# Circuit_Schematic.net
KiCad netlist of a schematic drawn in Altium Designer
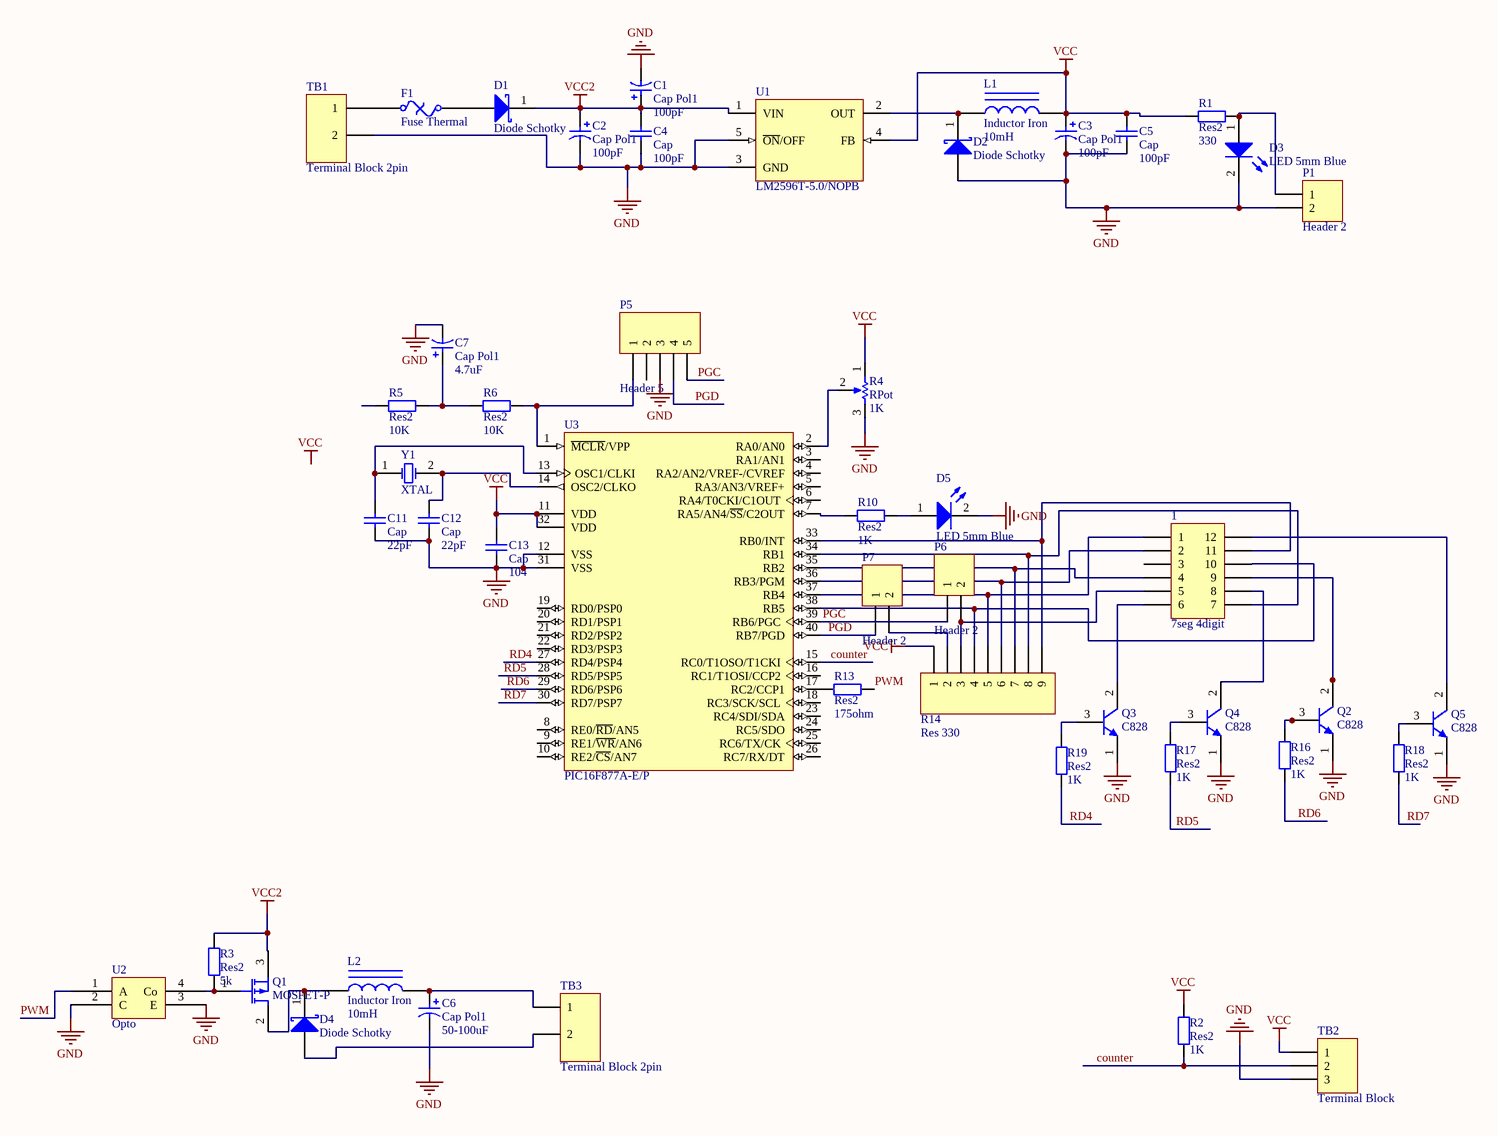
[diagram p0: Circuit Schematic.SchDoc]

(export (version "E")
  (design (tool "Eeschema 10.0.6"))
  (components
    (comp (ref "1")
      (value "7seg 4digit")
      (footprint "LEDDIP-12/QUAD")
      (description "Header, 6-Pin, Dual row")
      (fields (field (name "PUBLISHER") "Altium Limited"))
      (libsource (lib "Manh") (part "7seg 4digit"))
    )
    (comp (ref "C1")
      (value "Cap Pol1")
      (footprint "Manh:CAPPR2-5x7")
      (description "Polarized Capacitor (Radial)")
      (fields (field (name "ALTIUM_VALUE") "100pF") (field (name "PUBLISHER") "Altium Limited"))
      (libsource (lib "Manh") (part "Cap Pol1"))
    )
    (comp (ref "C2")
      (value "Cap Pol1")
      (footprint "CAPPR2.5-6.3x5/H.9")
      (description "Polarized Capacitor (Radial)")
      (fields (field (name "ALTIUM_VALUE") "100pF") (field (name "PUBLISHER") "Altium Limited"))
      (libsource (lib "Manh") (part "Cap Pol1"))
    )
    (comp (ref "C3")
      (value "Cap Pol1")
      (footprint "CAPPR2.5-6.3x5/H.9")
      (description "Polarized Capacitor (Radial)")
      (fields (field (name "ALTIUM_VALUE") "100pF") (field (name "PUBLISHER") "Altium Limited"))
      (libsource (lib "Manh") (part "Cap Pol1"))
    )
    (comp (ref "C4")
      (value "Cap")
      (footprint "CAPNTO3.18-4.83x2.67")
      (description "Capacitor")
      (fields (field (name "ALTIUM_VALUE") "100pF") (field (name "PUBLISHER") "Altium Limited"))
      (libsource (lib "Manh") (part "Cap"))
    )
    (comp (ref "C5")
      (value "Cap")
      (footprint "CAPNTO3.18-4.83x2.67")
      (description "Capacitor")
      (fields (field (name "ALTIUM_VALUE") "100pF") (field (name "PUBLISHER") "Altium Limited"))
      (libsource (lib "Manh") (part "Cap"))
    )
    (comp (ref "C6")
      (value "Cap Pol1")
      (footprint "CAPPR2.5-6.3x5/H.9")
      (description "Polarized Capacitor (Radial)")
      (fields (field (name "ALTIUM_VALUE") "50-100uF") (field (name "PUBLISHER") "Altium Limited"))
      (libsource (lib "Manh") (part "Cap Pol1"))
    )
    (comp (ref "C7")
      (value "Cap Pol1")
      (footprint "CAPPR2-5x7")
      (description "Polarized Capacitor (Radial)")
      (fields (field (name "ALTIUM_VALUE") "4.7uF") (field (name "PUBLISHER") "Altium Limited"))
      (libsource (lib "Manh") (part "Cap Pol1"))
    )
    (comp (ref "C11")
      (value "Cap")
      (footprint "CAPNTO3.18-4.83x2.67")
      (description "Capacitor")
      (fields (field (name "ALTIUM_VALUE") "22pF") (field (name "PUBLISHER") "Altium Limited"))
      (libsource (lib "Manh") (part "Cap"))
    )
    (comp (ref "C12")
      (value "Cap")
      (footprint "CAPNTO3.18-4.83x2.67")
      (description "Capacitor")
      (fields (field (name "ALTIUM_VALUE") "22pF") (field (name "PUBLISHER") "Altium Limited"))
      (libsource (lib "Manh") (part "Cap"))
    )
    (comp (ref "C13")
      (value "Cap")
      (footprint "CAPNTO3.18-4.83x2.67")
      (description "Capacitor")
      (fields (field (name "ALTIUM_VALUE") "104") (field (name "PUBLISHER") "Altium Limited"))
      (libsource (lib "Manh") (part "Cap"))
    )
    (comp (ref "D1")
      (value "Diode Schotky")
      (footprint "DO-201AD")
      (description "Schottky Rectifier")
      (fields (field (name "PUBLISHER") "Altium Limited"))
      (libsource (lib "Manh") (part "Diode Schotky"))
    )
    (comp (ref "D2")
      (value "Diode Schotky")
      (footprint "DO-41")
      (description "Schottky Rectifier")
      (fields (field (name "PUBLISHER") "Altium Limited"))
      (libsource (lib "Manh") (part "Diode Schotky"))
    )
    (comp (ref "D3")
      (value "LED 5mm Blue")
      (footprint "LED 5mm Blue")
      (description "Typical INFRARED GaAs LED")
      (fields (field (name "PUBLISHER") "Altium Limited"))
      (libsource (lib "Manh") (part "LED 5mm Blue"))
    )
    (comp (ref "D4")
      (value "Diode Schotky")
      (footprint "DO-41")
      (description "Schottky Rectifier")
      (fields (field (name "PUBLISHER") "Altium Limited"))
      (libsource (lib "Manh") (part "Diode Schotky"))
    )
    (comp (ref "D5")
      (value "LED 5mm Blue")
      (footprint "LED 5mm Blue")
      (description "Typical INFRARED GaAs LED")
      (fields (field (name "PUBLISHER") "Altium Limited"))
      (libsource (lib "Manh") (part "LED 5mm Blue"))
    )
    (comp (ref "F1")
      (value "Fuse Thermal")
      (footprint "PIN-W2/E2.8 -Manh")
      (description "Thermal Fuse")
      (fields (field (name "PUBLISHER") "Altium Limited"))
      (libsource (lib "Manh") (part "Fuse Thermal"))
    )
    (comp (ref "L1")
      (value "Inductor Iron")
      (footprint "Inductor power")
      (description "Magnetic-Core Inductor")
      (fields (field (name "ALTIUM_VALUE") "10mH") (field (name "PUBLISHER") "Altium Limited"))
      (libsource (lib "Manh") (part "Inductor Iron"))
    )
    (comp (ref "L2")
      (value "Inductor Iron")
      (footprint "Inductor power")
      (description "Magnetic-Core Inductor")
      (fields (field (name "ALTIUM_VALUE") "10mH") (field (name "PUBLISHER") "Altium Limited"))
      (libsource (lib "Manh") (part "Inductor Iron"))
    )
    (comp (ref "P1")
      (value "Header 2")
      (footprint "HDR1X2")
      (description "Header, 2-Pin")
      (fields (field (name "PUBLISHER") "Altium Limited"))
      (libsource (lib "Manh") (part "Header 2"))
    )
    (comp (ref "P5")
      (value "Header 5")
      (footprint "HDR1X5")
      (description "Header, 5-Pin")
      (fields (field (name "PUBLISHER") "Altium Limited"))
      (libsource (lib "Manh") (part "Header 5"))
    )
    (comp (ref "P6")
      (value "Header 2")
      (footprint "HDR1X2")
      (description "Header, 2-Pin")
      (fields (field (name "PUBLISHER") "Altium Limited"))
      (libsource (lib "") (part "Header 2_1"))
    )
    (comp (ref "P7")
      (value "Header 2")
      (footprint "HDR1X2")
      (description "Header, 2-Pin")
      (fields (field (name "PUBLISHER") "Altium Limited"))
      (libsource (lib "") (part "Header 2_1"))
    )
    (comp (ref "Q1")
      (value "MOSFET-P")
      (footprint "TO 220")
      (description "P-Channel MOSFET")
      (fields (field (name "PUBLISHER") "Altium Limited"))
      (libsource (lib "Manh") (part "MOSFET-P"))
    )
    (comp (ref "Q2")
      (value "C828")
      (footprint "TO-92-manh")
      (description "NPN General Purpose Amplifier")
      (fields (field (name "PUBLISHER") "Altium Limited"))
      (libsource (lib "Manh") (part "C828"))
    )
    (comp (ref "Q3")
      (value "C828")
      (footprint "TO-92-manh")
      (description "NPN General Purpose Amplifier")
      (fields (field (name "PUBLISHER") "Altium Limited"))
      (libsource (lib "Manh") (part "C828"))
    )
    (comp (ref "Q4")
      (value "C828")
      (footprint "TO-92-manh")
      (description "NPN General Purpose Amplifier")
      (fields (field (name "PUBLISHER") "Altium Limited"))
      (libsource (lib "Manh") (part "C828"))
    )
    (comp (ref "Q5")
      (value "C828")
      (footprint "TO-92-manh")
      (description "NPN General Purpose Amplifier")
      (fields (field (name "PUBLISHER") "Altium Limited"))
      (libsource (lib "Manh") (part "C828"))
    )
    (comp (ref "R1")
      (value "Res2")
      (footprint "AXIAL-0.4")
      (description "Resistor")
      (fields (field (name "ALTIUM_VALUE") "330") (field (name "PUBLISHER") "Altium Limited"))
      (libsource (lib "Manh") (part "Res2"))
    )
    (comp (ref "R2")
      (value "Res2")
      (footprint "AXIAL-0.4")
      (description "Resistor")
      (fields (field (name "ALTIUM_VALUE") "1K") (field (name "PUBLISHER") "Altium Limited"))
      (libsource (lib "") (part "Res2_2"))
    )
    (comp (ref "R3")
      (value "Res2")
      (footprint "AXIAL-0.4")
      (description "Resistor")
      (fields (field (name "ALTIUM_VALUE") "5k") (field (name "PUBLISHER") "Altium Limited"))
      (libsource (lib "") (part "Res2_1"))
    )
    (comp (ref "R4")
      (value "RPot")
      (footprint "Variable Resistor")
      (description "Potentiometer")
      (fields (field (name "ALTIUM_VALUE") "1K") (field (name "PUBLISHER") "Altium Limited"))
      (libsource (lib "Manh") (part "RPot"))
    )
    (comp (ref "R5")
      (value "Res2")
      (footprint "AXIAL-0.4")
      (description "Resistor")
      (fields (field (name "ALTIUM_VALUE") "10K") (field (name "PUBLISHER") "Altium Limited"))
      (libsource (lib "Manh") (part "Res2"))
    )
    (comp (ref "R6")
      (value "Res2")
      (footprint "AXIAL-0.4")
      (description "Resistor")
      (fields (field (name "ALTIUM_VALUE") "10K") (field (name "PUBLISHER") "Altium Limited"))
      (libsource (lib "Manh") (part "Res2"))
    )
    (comp (ref "R10")
      (value "Res2")
      (footprint "AXIAL-0.4")
      (description "Resistor")
      (fields (field (name "ALTIUM_VALUE") "1K") (field (name "PUBLISHER") "Altium Limited"))
      (libsource (lib "Manh") (part "Res2"))
    )
    (comp (ref "R13")
      (value "Res2")
      (footprint "AXIAL-0.4")
      (description "Resistor")
      (fields (field (name "ALTIUM_VALUE") "175ohm") (field (name "PUBLISHER") "Altium Limited"))
      (libsource (lib "") (part "Res2_3"))
    )
    (comp (ref "R14")
      (value "Res 330")
      (footprint "Res array 8")
      (description "Header, 9-Pin")
      (fields (field (name "PUBLISHER") "Altium Limited"))
      (libsource (lib "Manh") (part "Res array 8"))
    )
    (comp (ref "R16")
      (value "Res2")
      (footprint "AXIAL-0.4")
      (description "Resistor")
      (fields (field (name "ALTIUM_VALUE") "1K") (field (name "PUBLISHER") "Altium Limited"))
      (libsource (lib "") (part "Res2_1"))
    )
    (comp (ref "R17")
      (value "Res2")
      (footprint "AXIAL-0.4")
      (description "Resistor")
      (fields (field (name "ALTIUM_VALUE") "1K") (field (name "PUBLISHER") "Altium Limited"))
      (libsource (lib "") (part "Res2_1"))
    )
    (comp (ref "R18")
      (value "Res2")
      (footprint "AXIAL-0.4")
      (description "Resistor")
      (fields (field (name "ALTIUM_VALUE") "1K") (field (name "PUBLISHER") "Altium Limited"))
      (libsource (lib "") (part "Res2_1"))
    )
    (comp (ref "R19")
      (value "Res2")
      (footprint "AXIAL-0.4")
      (description "Resistor")
      (fields (field (name "ALTIUM_VALUE") "1K") (field (name "PUBLISHER") "Altium Limited"))
      (libsource (lib "") (part "Res2_1"))
    )
    (comp (ref "TB1")
      (value "Terminal Block 2pin")
      (footprint "Screw Terminal Block 2pin 5mm")
      (fields (field (name "PUBLISHER") "Altium Limited"))
      (libsource (lib "Manh") (part "Terminal Block 2pin"))
    )
    (comp (ref "TB2")
      (value "Terminal Block")
      (footprint "Screw Terminal Block 3pin 5mm")
      (description "Terminal Block 3pin")
      (fields (field (name "PUBLISHER") "Altium Limited"))
      (libsource (lib "Manh") (part "Terminal Block 3pin"))
    )
    (comp (ref "TB3")
      (value "Terminal Block 2pin")
      (footprint "Screw Terminal Block 2pin 5mm")
      (fields (field (name "PUBLISHER") "Altium Limited"))
      (libsource (lib "") (part "Terminal Block 2pin_1"))
    )
    (comp (ref "U1")
      (value "LM2596T-5.0/NOPB")
      (footprint "T05D")
      (description "SIMPLE SWITCHER® Power Converter 150 KHz 3A Step-Down Voltage Regulator, 5-pin TO-220, Pb-Free")
      (fields
        (field (name "MANUFACTURER") "National Semiconductor")
        (field (name "PUBLISHER") "Altium Limited")
      )
      (libsource (lib "Manh") (part "LM2596T-5.0/NOPB"))
    )
    (comp (ref "U2") (value "Opto") (footprint "DIP-6 -v2") (libsource (lib "Manh") (part "Opto 1")))
    (comp (ref "U3")
      (value "PIC16F877A-E/P")
      (footprint "Manh:PDIP600-40")
      (fields (field (name "PUBLISHER") "Altium Limited"))
      (libsource (lib "Manh") (part "PIC16F877A-E/P"))
    )
    (comp (ref "Y1")
      (value "XTAL")
      (footprint "R38")
      (description "Crystal Oscillator")
      (fields (field (name "PUBLISHER") "Altium Limited"))
      (libsource (lib "Manh") (part "XTAL"))
    )
  )
  (nets
    (net (code "1") (name "/PGC") (class "Default")
      (node (ref "P5") (pin "5") (pinfunction "5_5") (pintype "passive"))
      (node (ref "P6") (pin "1") (pinfunction "1_1") (pintype "passive"))
      (node (ref "U3") (pin "39") (pinfunction "RB6/PGC_39") (pintype "bidirectional"))
    )
    (net (code "2") (name "/PGD") (class "Default")
      (node (ref "P5") (pin "4") (pinfunction "4_4") (pintype "passive"))
      (node (ref "P7") (pin "1") (pinfunction "1_1") (pintype "passive"))
      (node (ref "U3") (pin "40") (pinfunction "RB7/PGD_40") (pintype "bidirectional"))
    )
    (net (code "3") (name "/PWM") (class "Default")
      (node (ref "R13") (pin "1") (pinfunction "1_1") (pintype "passive"))
      (node (ref "U2") (pin "1") (pinfunction "A_1") (pintype "passive"))
    )
    (net (code "4") (name "/RD4") (class "Default")
      (node (ref "R19") (pin "1") (pinfunction "1_1") (pintype "passive"))
      (node (ref "U3") (pin "27") (pinfunction "RD4/PSP4_27") (pintype "bidirectional"))
    )
    (net (code "5") (name "/RD5") (class "Default")
      (node (ref "R17") (pin "1") (pinfunction "1_1") (pintype "passive"))
      (node (ref "U3") (pin "28") (pinfunction "RD5/PSP5_28") (pintype "bidirectional"))
    )
    (net (code "6") (name "/RD6") (class "Default")
      (node (ref "R16") (pin "1") (pinfunction "1_1") (pintype "passive"))
      (node (ref "U3") (pin "29") (pinfunction "RD6/PSP6_29") (pintype "bidirectional"))
    )
    (net (code "7") (name "/RD7") (class "Default")
      (node (ref "R18") (pin "1") (pinfunction "1_1") (pintype "passive"))
      (node (ref "U3") (pin "30") (pinfunction "RD7/PSP7_30") (pintype "bidirectional"))
    )
    (net (code "8") (name "/counter") (class "Default")
      (node (ref "R2") (pin "2") (pinfunction "2_2") (pintype "passive"))
      (node (ref "TB2") (pin "2") (pinfunction "2_2") (pintype "passive"))
      (node (ref "U3") (pin "15") (pinfunction "RC0/T1OSO/T1CKI_15") (pintype "bidirectional"))
    )
    (net (code "9") (name "GND") (class "Default")
      (node (ref "C1") (pin "2") (pinfunction "2_2") (pintype "passive"))
      (node (ref "C11") (pin "1") (pinfunction "1_1") (pintype "passive"))
      (node (ref "C12") (pin "1") (pinfunction "1_1") (pintype "passive"))
      (node (ref "C13") (pin "1") (pinfunction "1_1") (pintype "passive"))
      (node (ref "C2") (pin "2") (pinfunction "2_2") (pintype "passive"))
      (node (ref "C3") (pin "2") (pinfunction "2_2") (pintype "passive"))
      (node (ref "C4") (pin "1") (pinfunction "1_1") (pintype "passive"))
      (node (ref "C5") (pin "1") (pinfunction "1_1") (pintype "passive"))
      (node (ref "C6") (pin "2") (pinfunction "2_2") (pintype "passive"))
      (node (ref "C7") (pin "2") (pinfunction "2_2") (pintype "passive"))
      (node (ref "D2") (pin "2") (pinfunction "A_2") (pintype "passive"))
      (node (ref "D3") (pin "2") (pinfunction "K_2") (pintype "passive"))
      (node (ref "D5") (pin "2") (pinfunction "K_2") (pintype "passive"))
      (node (ref "P1") (pin "2") (pinfunction "2_2") (pintype "passive"))
      (node (ref "P5") (pin "3") (pinfunction "3_3") (pintype "passive"))
      (node (ref "Q2") (pin "1") (pinfunction "E_1") (pintype "passive"))
      (node (ref "Q3") (pin "1") (pinfunction "E_1") (pintype "passive"))
      (node (ref "Q4") (pin "1") (pinfunction "E_1") (pintype "passive"))
      (node (ref "Q5") (pin "1") (pinfunction "E_1") (pintype "passive"))
      (node (ref "R4") (pin "3") (pinfunction "BOT_3") (pintype "passive"))
      (node (ref "TB1") (pin "2") (pinfunction "2_2") (pintype "passive"))
      (node (ref "TB2") (pin "3") (pinfunction "3_3") (pintype "passive"))
      (node (ref "U1") (pin "3") (pinfunction "GND_3") (pintype "power_in"))
      (node (ref "U1") (pin "5") (pinfunction "~{ON}/OFF_5") (pintype "input"))
      (node (ref "U2") (pin "2") (pinfunction "C_2") (pintype "passive"))
      (node (ref "U2") (pin "3") (pinfunction "E_3") (pintype "passive"))
      (node (ref "U3") (pin "12") (pinfunction "VSS_12") (pintype "power_in"))
      (node (ref "U3") (pin "31") (pinfunction "VSS_31") (pintype "power_in"))
    )
    (net (code "10") (name "Net-(1-Pad5)") (class "Default")
      (node (ref "1") (pin "5") (pinfunction "5_5") (pintype "passive"))
      (node (ref "P6") (pin "2") (pinfunction "2_2") (pintype "passive"))
      (node (ref "R14") (pin "3") (pinfunction "3_3") (pintype "passive"))
    )
    (net (code "11") (name "Net-(C6-Pad1)") (class "Default")
      (node (ref "C6") (pin "1") (pinfunction "1_1") (pintype "passive"))
      (node (ref "L2") (pin "2") (pinfunction "2_2") (pintype "passive"))
      (node (ref "TB3") (pin "1") (pinfunction "1_1") (pintype "passive"))
    )
    (net (code "12") (name "Net-(C7-Pad1)") (class "Default")
      (node (ref "C7") (pin "1") (pinfunction "1_1") (pintype "passive"))
      (node (ref "R5") (pin "2") (pinfunction "2_2") (pintype "passive"))
      (node (ref "R6") (pin "1") (pinfunction "1_1") (pintype "passive"))
    )
    (net (code "13") (name "Net-(D1-A)") (class "Default")
      (node (ref "D1") (pin "2") (pinfunction "A_2") (pintype "passive"))
      (node (ref "F1") (pin "2") (pinfunction "2_2") (pintype "passive"))
    )
    (net (code "14") (name "Net-(D2-K)") (class "Default")
      (node (ref "D2") (pin "1") (pinfunction "K_1") (pintype "passive"))
      (node (ref "L1") (pin "1") (pinfunction "1_1") (pintype "passive"))
      (node (ref "U1") (pin "2") (pinfunction "OUT_2") (pintype "power_in"))
    )
    (net (code "15") (name "Net-(D3-A)") (class "Default")
      (node (ref "D3") (pin "1") (pinfunction "A_1") (pintype "passive"))
      (node (ref "P1") (pin "1") (pinfunction "1_1") (pintype "passive"))
      (node (ref "R1") (pin "2") (pinfunction "2_2") (pintype "passive"))
    )
    (net (code "16") (name "Net-(D4-A)") (class "Default")
      (node (ref "D4") (pin "2") (pinfunction "A_2") (pintype "passive"))
      (node (ref "TB3") (pin "2") (pinfunction "2_2") (pintype "passive"))
    )
    (net (code "17") (name "Net-(D4-K)") (class "Default")
      (node (ref "D4") (pin "1") (pinfunction "K_1") (pintype "passive"))
      (node (ref "L2") (pin "1") (pinfunction "1_1") (pintype "passive"))
      (node (ref "Q1") (pin "2") (pinfunction "D_2") (pintype "passive"))
    )
    (net (code "18") (name "Net-(D5-A)") (class "Default")
      (node (ref "D5") (pin "1") (pinfunction "A_1") (pintype "passive"))
      (node (ref "R10") (pin "2") (pinfunction "2_2") (pintype "passive"))
    )
    (net (code "19") (name "Net-(F1-Pad1)") (class "Default")
      (node (ref "F1") (pin "1") (pinfunction "1_1") (pintype "passive"))
      (node (ref "TB1") (pin "1") (pinfunction "1_1") (pintype "passive"))
    )
    (net (code "20") (name "Net-(P7-Pad2)") (class "Default")
      (node (ref "P7") (pin "2") (pinfunction "2_2") (pintype "passive"))
      (node (ref "R14") (pin "2") (pinfunction "2_2") (pintype "passive"))
    )
    (net (code "21") (name "Net-(Q1-G)") (class "Default")
      (node (ref "Q1") (pin "1") (pinfunction "G_1") (pintype "passive"))
      (node (ref "R3") (pin "1") (pinfunction "1_1") (pintype "passive"))
      (node (ref "U2") (pin "4") (pinfunction "Co_4") (pintype "passive"))
    )
    (net (code "22") (name "Net-(Q2-B)") (class "Default")
      (node (ref "Q2") (pin "3") (pinfunction "B_3") (pintype "passive"))
      (node (ref "R16") (pin "2") (pinfunction "2_2") (pintype "passive"))
    )
    (net (code "23") (name "Net-(Q2-C)") (class "Default")
      (node (ref "1") (pin "9") (pinfunction "9_9") (pintype "passive"))
      (node (ref "Q2") (pin "2") (pinfunction "C_2") (pintype "passive"))
    )
    (net (code "24") (name "Net-(Q3-B)") (class "Default")
      (node (ref "Q3") (pin "3") (pinfunction "B_3") (pintype "passive"))
      (node (ref "R19") (pin "2") (pinfunction "2_2") (pintype "passive"))
    )
    (net (code "25") (name "Net-(Q3-C)") (class "Default")
      (node (ref "1") (pin "6") (pinfunction "6_6") (pintype "passive"))
      (node (ref "Q3") (pin "2") (pinfunction "C_2") (pintype "passive"))
    )
    (net (code "26") (name "Net-(Q4-B)") (class "Default")
      (node (ref "Q4") (pin "3") (pinfunction "B_3") (pintype "passive"))
      (node (ref "R17") (pin "2") (pinfunction "2_2") (pintype "passive"))
    )
    (net (code "27") (name "Net-(Q4-C)") (class "Default")
      (node (ref "1") (pin "8") (pinfunction "8_8") (pintype "passive"))
      (node (ref "Q4") (pin "2") (pinfunction "C_2") (pintype "passive"))
    )
    (net (code "28") (name "Net-(Q5-B)") (class "Default")
      (node (ref "Q5") (pin "3") (pinfunction "B_3") (pintype "passive"))
      (node (ref "R18") (pin "2") (pinfunction "2_2") (pintype "passive"))
    )
    (net (code "29") (name "Net-(Q5-C)") (class "Default")
      (node (ref "1") (pin "12") (pinfunction "12_12") (pintype "passive"))
      (node (ref "Q5") (pin "2") (pinfunction "C_2") (pintype "passive"))
    )
    (net (code "30") (name "Net-(R4-TAP)") (class "Default")
      (node (ref "R4") (pin "2") (pinfunction "TAP_2") (pintype "passive"))
      (node (ref "U3") (pin "2") (pinfunction "RA0/AN0_2") (pintype "bidirectional"))
    )
    (net (code "31") (name "Net-(U3-OSC1{slash}CLKI)") (class "Default")
      (node (ref "C11") (pin "2") (pinfunction "2_2") (pintype "passive"))
      (node (ref "U3") (pin "13") (pinfunction "OSC1/CLKI_13") (pintype "input"))
      (node (ref "Y1") (pin "1") (pinfunction "OSC1_1") (pintype "passive"))
    )
    (net (code "32") (name "Net-(U3-OSC2{slash}CLKO)") (class "Default")
      (node (ref "C12") (pin "2") (pinfunction "2_2") (pintype "passive"))
      (node (ref "U3") (pin "14") (pinfunction "OSC2/CLKO_14") (pintype "output"))
      (node (ref "Y1") (pin "2") (pinfunction "OSC2_2") (pintype "passive"))
    )
    (net (code "33") (name "Net-(U3-RA5{slash}AN4{slash}~{SS}{slash}C2OUT)") (class "Default")
      (node (ref "R10") (pin "1") (pinfunction "1_1") (pintype "passive"))
      (node (ref "U3") (pin "7") (pinfunction "RA5/AN4/~{SS}/C2OUT_7") (pintype "bidirectional"))
    )
    (net (code "34") (name "Net-(U3-RB0{slash}INT)") (class "Default")
      (node (ref "1") (pin "11") (pinfunction "11_11") (pintype "passive"))
      (node (ref "R14") (pin "9") (pinfunction "9_9") (pintype "passive"))
      (node (ref "U3") (pin "33") (pinfunction "RB0/INT_33") (pintype "bidirectional"))
    )
    (net (code "35") (name "Net-(U3-RB1)") (class "Default")
      (node (ref "1") (pin "7") (pinfunction "7_7") (pintype "passive"))
      (node (ref "R14") (pin "8") (pinfunction "8_8") (pintype "passive"))
      (node (ref "U3") (pin "34") (pinfunction "RB1_34") (pintype "bidirectional"))
    )
    (net (code "36") (name "Net-(U3-RB2)") (class "Default")
      (node (ref "1") (pin "4") (pinfunction "4_4") (pintype "passive"))
      (node (ref "R14") (pin "7") (pinfunction "7_7") (pintype "passive"))
      (node (ref "U3") (pin "35") (pinfunction "RB2_35") (pintype "bidirectional"))
    )
    (net (code "37") (name "Net-(U3-RB3{slash}PGM)") (class "Default")
      (node (ref "1") (pin "2") (pinfunction "2_2") (pintype "passive"))
      (node (ref "R14") (pin "6") (pinfunction "6_6") (pintype "passive"))
      (node (ref "U3") (pin "36") (pinfunction "RB3/PGM_36") (pintype "bidirectional"))
    )
    (net (code "38") (name "Net-(U3-RB4)") (class "Default")
      (node (ref "1") (pin "1") (pinfunction "1_1") (pintype "passive"))
      (node (ref "R14") (pin "5") (pinfunction "5_5") (pintype "passive"))
      (node (ref "U3") (pin "37") (pinfunction "RB4_37") (pintype "bidirectional"))
    )
    (net (code "39") (name "Net-(U3-RB5)") (class "Default")
      (node (ref "1") (pin "10") (pinfunction "10_10") (pintype "passive"))
      (node (ref "R14") (pin "4") (pinfunction "4_4") (pintype "passive"))
      (node (ref "U3") (pin "38") (pinfunction "RB5_38") (pintype "bidirectional"))
    )
    (net (code "40") (name "Net-(U3-RC2{slash}CCP1)") (class "Default")
      (node (ref "R13") (pin "2") (pinfunction "2_2") (pintype "passive"))
      (node (ref "U3") (pin "17") (pinfunction "RC2/CCP1_17") (pintype "bidirectional"))
    )
    (net (code "41") (name "Net-(U3-~{MCLR}{slash}VPP)") (class "Default")
      (node (ref "P5") (pin "1") (pinfunction "1_1") (pintype "passive"))
      (node (ref "R6") (pin "2") (pinfunction "2_2") (pintype "passive"))
      (node (ref "U3") (pin "1") (pinfunction "~{MCLR}/VPP_1") (pintype "input"))
    )
    (net (code "42") (name "VCC") (class "Default")
      (node (ref "C13") (pin "2") (pinfunction "2_2") (pintype "passive"))
      (node (ref "C3") (pin "1") (pinfunction "1_1") (pintype "passive"))
      (node (ref "C5") (pin "2") (pinfunction "2_2") (pintype "passive"))
      (node (ref "L1") (pin "2") (pinfunction "2_2") (pintype "passive"))
      (node (ref "R1") (pin "1") (pinfunction "1_1") (pintype "passive"))
      (node (ref "R14") (pin "1") (pinfunction "1_1") (pintype "passive"))
      (node (ref "R2") (pin "1") (pinfunction "1_1") (pintype "passive"))
      (node (ref "R4") (pin "1") (pinfunction "TOP_1") (pintype "passive"))
      (node (ref "TB2") (pin "1") (pinfunction "1_1") (pintype "passive"))
      (node (ref "U1") (pin "4") (pinfunction "FB_4") (pintype "input"))
      (node (ref "U3") (pin "11") (pinfunction "VDD_11") (pintype "power_in"))
      (node (ref "U3") (pin "32") (pinfunction "VDD_32") (pintype "power_in"))
    )
    (net (code "43") (name "VCC2") (class "Default")
      (node (ref "C1") (pin "1") (pinfunction "1_1") (pintype "passive"))
      (node (ref "C2") (pin "1") (pinfunction "1_1") (pintype "passive"))
      (node (ref "C4") (pin "2") (pinfunction "2_2") (pintype "passive"))
      (node (ref "D1") (pin "1") (pinfunction "K_1") (pintype "passive"))
      (node (ref "Q1") (pin "3") (pinfunction "S_3") (pintype "passive"))
      (node (ref "R3") (pin "2") (pinfunction "2_2") (pintype "passive"))
      (node (ref "U1") (pin "1") (pinfunction "VIN_1") (pintype "power_in"))
    )
    (net (code "44") (name "unconnected-(1-Pad3)") (class "Default")
      (node (ref "1") (pin "3") (pinfunction "3_3") (pintype "passive"))
    )
    (net (code "45") (name "unconnected-(P5-Pad2)") (class "Default")
      (node (ref "P5") (pin "2") (pinfunction "2_2") (pintype "passive"))
    )
    (net (code "46") (name "unconnected-(R5-Pad1)") (class "Default")
      (node (ref "R5") (pin "1") (pinfunction "1_1") (pintype "passive"))
    )
    (net (code "47") (name "unconnected-(U3-RA1{slash}AN1-Pad3)") (class "Default")
      (node (ref "U3") (pin "3") (pinfunction "RA1/AN1_3") (pintype "bidirectional"))
    )
    (net (code "48") (name "unconnected-(U3-RA2{slash}AN2{slash}VREF-{slash}CVREF-Pad4)") (class "Default")
      (node (ref "U3") (pin "4") (pinfunction "RA2/AN2/VREF-/CVREF_4") (pintype "bidirectional"))
    )
    (net (code "49") (name "unconnected-(U3-RA3{slash}AN3{slash}VREF+-Pad5)") (class "Default")
      (node (ref "U3") (pin "5") (pinfunction "RA3/AN3/VREF+_5") (pintype "bidirectional"))
    )
    (net (code "50") (name "unconnected-(U3-RA4{slash}T0CKI{slash}C1OUT-Pad6)") (class "Default")
      (node (ref "U3") (pin "6") (pinfunction "RA4/T0CKI/C1OUT_6") (pintype "bidirectional"))
    )
    (net (code "51") (name "unconnected-(U3-RC1{slash}T1OSI{slash}CCP2-Pad16)") (class "Default")
      (node (ref "U3") (pin "16") (pinfunction "RC1/T1OSI/CCP2_16") (pintype "bidirectional"))
    )
    (net (code "52") (name "unconnected-(U3-RC3{slash}SCK{slash}SCL-Pad18)") (class "Default")
      (node (ref "U3") (pin "18") (pinfunction "RC3/SCK/SCL_18") (pintype "bidirectional"))
    )
    (net (code "53") (name "unconnected-(U3-RC4{slash}SDI{slash}SDA-Pad23)") (class "Default")
      (node (ref "U3") (pin "23") (pinfunction "RC4/SDI/SDA_23") (pintype "bidirectional"))
    )
    (net (code "54") (name "unconnected-(U3-RC5{slash}SDO-Pad24)") (class "Default")
      (node (ref "U3") (pin "24") (pinfunction "RC5/SDO_24") (pintype "bidirectional"))
    )
    (net (code "55") (name "unconnected-(U3-RC6{slash}TX{slash}CK-Pad25)") (class "Default")
      (node (ref "U3") (pin "25") (pinfunction "RC6/TX/CK_25") (pintype "bidirectional"))
    )
    (net (code "56") (name "unconnected-(U3-RC7{slash}RX{slash}DT-Pad26)") (class "Default")
      (node (ref "U3") (pin "26") (pinfunction "RC7/RX/DT_26") (pintype "bidirectional"))
    )
    (net (code "57") (name "unconnected-(U3-RD0{slash}PSP0-Pad19)") (class "Default")
      (node (ref "U3") (pin "19") (pinfunction "RD0/PSP0_19") (pintype "bidirectional"))
    )
    (net (code "58") (name "unconnected-(U3-RD1{slash}PSP1-Pad20)") (class "Default")
      (node (ref "U3") (pin "20") (pinfunction "RD1/PSP1_20") (pintype "bidirectional"))
    )
    (net (code "59") (name "unconnected-(U3-RD2{slash}PSP2-Pad21)") (class "Default")
      (node (ref "U3") (pin "21") (pinfunction "RD2/PSP2_21") (pintype "bidirectional"))
    )
    (net (code "60") (name "unconnected-(U3-RD3{slash}PSP3-Pad22)") (class "Default")
      (node (ref "U3") (pin "22") (pinfunction "RD3/PSP3_22") (pintype "bidirectional"))
    )
    (net (code "61") (name "unconnected-(U3-RE0{slash}~{RD}{slash}AN5-Pad8)") (class "Default")
      (node (ref "U3") (pin "8") (pinfunction "RE0/~{RD}/AN5_8") (pintype "bidirectional"))
    )
    (net (code "62") (name "unconnected-(U3-RE1{slash}~{WR}{slash}AN6-Pad9)") (class "Default")
      (node (ref "U3") (pin "9") (pinfunction "RE1/~{WR}/AN6_9") (pintype "bidirectional"))
    )
    (net (code "63") (name "unconnected-(U3-RE2{slash}~{CS}{slash}AN7-Pad10)") (class "Default")
      (node (ref "U3") (pin "10") (pinfunction "RE2/~{CS}/AN7_10") (pintype "bidirectional"))
    )
  )
)
